# MotorVSense.net
KiCad netlist of a schematic drawn in Altium Designer
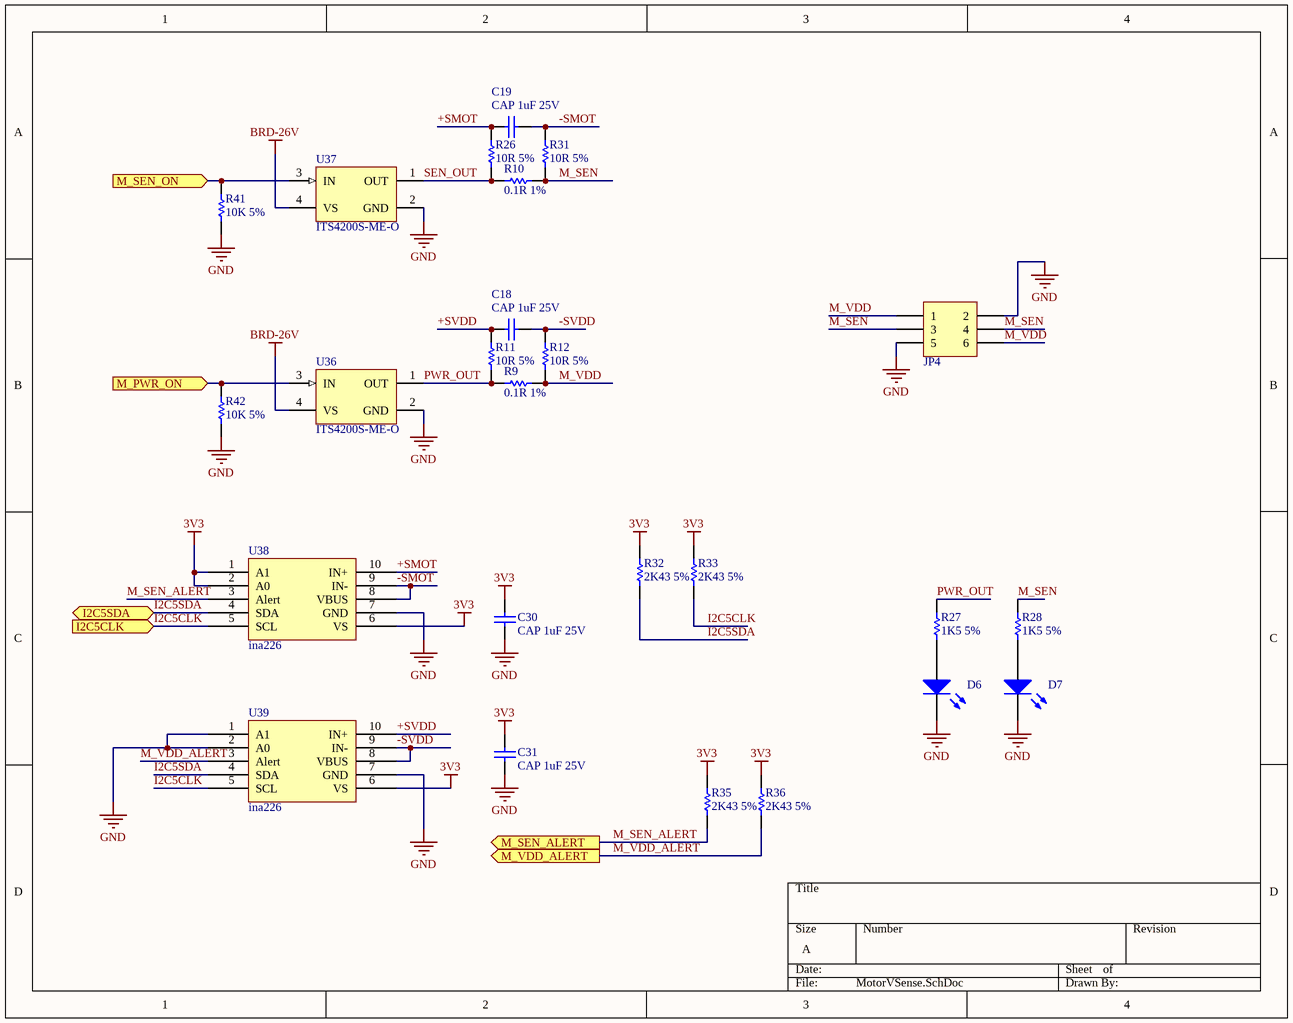
[diagram p0: MotorVSense.SchDoc]

(export (version "E")
  (design (tool "Eeschema 10.0.6"))
  (components
    (comp (ref "C18")
      (value "CAP 1uF 25V")
      (footprint "CAPC0603(1608)100_M")
      (description "CAP 1uF 25V Â±0.25pF 0603 (1608 Metric) Thickness 1mm SMD")
      (fields (field (name "TOLERANCE") "Â±0.25pF"))
      (libsource (lib "Altium Content Vault") (part "CMP-1035-00037-1"))
    )
    (comp (ref "C19")
      (value "CAP 1uF 25V")
      (footprint "CAPC0603(1608)100_M")
      (description "CAP 1uF 25V Â±0.25pF 0603 (1608 Metric) Thickness 1mm SMD")
      (fields (field (name "TOLERANCE") "Â±0.25pF"))
      (libsource (lib "Altium Content Vault") (part "CMP-1035-00037-1"))
    )
    (comp (ref "C30")
      (value "CAP 1uF 25V")
      (footprint "CAPC0603(1608)100_M")
      (description "CAP 1uF 25V Â±0.25pF 0603 (1608 Metric) Thickness 1mm SMD")
      (fields (field (name "TOLERANCE") "Â±0.25pF"))
      (libsource (lib "Altium Content Vault") (part "CMP-1035-00037-1"))
    )
    (comp (ref "C31")
      (value "CAP 1uF 25V")
      (footprint "CAPC0603(1608)100_M")
      (description "CAP 1uF 25V Â±0.25pF 0603 (1608 Metric) Thickness 1mm SMD")
      (fields (field (name "TOLERANCE") "Â±0.25pF"))
      (libsource (lib "Altium Content Vault") (part "CMP-1035-00037-1"))
    )
    (comp (ref "D6")
      (value "LED")
      (footprint "LED-0603")
      (description "Typical RED, GREEN, YELLOW, AMBER GaAs LED")
      (fields (field (name "PUBLISHER") "Altium Limited"))
      (libsource (lib "HSBNE-Vend") (part "LED"))
    )
    (comp (ref "D7")
      (value "LED")
      (footprint "LED-0603")
      (description "Typical RED, GREEN, YELLOW, AMBER GaAs LED")
      (fields (field (name "PUBLISHER") "Altium Limited"))
      (libsource (lib "HSBNE-Vend") (part "LED"))
    )
    (comp (ref "JP4")
      (value "Header 3x2 2.54mm")
      (footprint "2X3")
      (description "Header, 6-Pin")
      (libsource (lib "HSBNE-Vend") (part "Header 3x2"))
    )
    (comp (ref "R9")
      (value "0.1R 1%")
      (footprint "RESC2010(5025)_M")
      (description "0.1R 2010 1%")
      (fields (field (name "TOLERANCE") "None"))
      (libsource (lib "Altium Content Vault") (part "CMP-1017-00001-1"))
    )
    (comp (ref "R10")
      (value "0.1R 1%")
      (footprint "RESC2010(5025)_M")
      (description "0.1R 2010 1%")
      (fields (field (name "TOLERANCE") "None"))
      (libsource (lib "Altium Content Vault") (part "CMP-1017-00001-1"))
    )
    (comp (ref "R11")
      (value "10R 5%")
      (footprint "RESC0603(1608)_M")
      (description "10R 0.1W 5% 0603 (1608 Metric)  SMD")
      (fields (field (name "TOLERANCE") "5 %") (field (name "POWER") "0.1 W"))
      (libsource (lib "Altium Content Vault") (part "CMP-1012-00026-1"))
    )
    (comp (ref "R12")
      (value "10R 5%")
      (footprint "RESC0603(1608)_M")
      (description "10R 0.1W 5% 0603 (1608 Metric)  SMD")
      (fields (field (name "TOLERANCE") "5 %") (field (name "POWER") "0.1 W"))
      (libsource (lib "Altium Content Vault") (part "CMP-1012-00026-1"))
    )
    (comp (ref "R26")
      (value "10R 5%")
      (footprint "RESC0603(1608)_M")
      (description "10R 0.1W 5% 0603 (1608 Metric)  SMD")
      (fields (field (name "TOLERANCE") "5 %") (field (name "POWER") "0.1 W"))
      (libsource (lib "Altium Content Vault") (part "CMP-1012-00026-1"))
    )
    (comp (ref "R27")
      (value "1K5 5%")
      (footprint "RESC0603(1608)_M")
      (description "1K5 0.1W 5% 0603 (1608 Metric)  SMD")
      (fields (field (name "POWER") "0.1 W") (field (name "TOLERANCE") "5 %"))
      (libsource (lib "Altium Content Vault") (part "CMP-1012-00078-1"))
    )
    (comp (ref "R28")
      (value "1K5 5%")
      (footprint "RESC0603(1608)_M")
      (description "1K5 0.1W 5% 0603 (1608 Metric)  SMD")
      (fields (field (name "POWER") "0.1 W") (field (name "TOLERANCE") "5 %"))
      (libsource (lib "Altium Content Vault") (part "CMP-1012-00078-1"))
    )
    (comp (ref "R31")
      (value "10R 5%")
      (footprint "RESC0603(1608)_M")
      (description "10R 0.1W 5% 0603 (1608 Metric)  SMD")
      (fields (field (name "TOLERANCE") "5 %") (field (name "POWER") "0.1 W"))
      (libsource (lib "Altium Content Vault") (part "CMP-1012-00026-1"))
    )
    (comp (ref "R32")
      (value "2K43 5%")
      (footprint "RESC0603(1608)_M")
      (description "2K43 0.1W 5% 0603 (1608 Metric)  SMD")
      (fields (field (name "TOLERANCE") "5 %") (field (name "POWER") "0.1 W"))
      (libsource (lib "Altium Content Vault") (part "CMP-1012-00083-1"))
    )
    (comp (ref "R33")
      (value "2K43 5%")
      (footprint "RESC0603(1608)_M")
      (description "2K43 0.1W 5% 0603 (1608 Metric)  SMD")
      (fields (field (name "TOLERANCE") "5 %") (field (name "POWER") "0.1 W"))
      (libsource (lib "Altium Content Vault") (part "CMP-1012-00083-1"))
    )
    (comp (ref "R35")
      (value "2K43 5%")
      (footprint "RESC0603(1608)_M")
      (description "2K43 0.1W 5% 0603 (1608 Metric)  SMD")
      (fields (field (name "TOLERANCE") "5 %") (field (name "POWER") "0.1 W"))
      (libsource (lib "Altium Content Vault") (part "CMP-1012-00083-1"))
    )
    (comp (ref "R36")
      (value "2K43 5%")
      (footprint "RESC0603(1608)_M")
      (description "2K43 0.1W 5% 0603 (1608 Metric)  SMD")
      (fields (field (name "TOLERANCE") "5 %") (field (name "POWER") "0.1 W"))
      (libsource (lib "Altium Content Vault") (part "CMP-1012-00083-1"))
    )
    (comp (ref "R41")
      (value "10K 5%")
      (footprint "RESC0603(1608)_M")
      (description "10K 0.1W 5% 0603 (1608 Metric)  SMD")
      (fields (field (name "TOLERANCE") "5 %") (field (name "POWER") "0.1 W"))
      (libsource (lib "Altium Content Vault") (part "CMP-1012-00098-1"))
    )
    (comp (ref "R42")
      (value "10K 5%")
      (footprint "RESC0603(1608)_M")
      (description "10K 0.1W 5% 0603 (1608 Metric)  SMD")
      (fields (field (name "TOLERANCE") "5 %") (field (name "POWER") "0.1 W"))
      (libsource (lib "Altium Content Vault") (part "CMP-1012-00098-1"))
    )
    (comp (ref "U36")
      (value "ITS4200S-ME-O")
      (footprint "INF-SOT223_M")
      (description "Smart High-Side NMOS-Power Switch, 11 to 45 V Operating, -40 to 125 degC, SOT223, Reel, Green")
      (fields (field (name "MANUFACTURER") "Infineon"))
      (libsource (lib "Altium Content Vault") (part "INF-ITS4200S-ME-X-SOT223-4"))
    )
    (comp (ref "U37")
      (value "ITS4200S-ME-O")
      (footprint "INF-SOT223_M")
      (description "Smart High-Side NMOS-Power Switch, 11 to 45 V Operating, -40 to 125 degC, SOT223, Reel, Green")
      (fields (field (name "MANUFACTURER") "Infineon"))
      (libsource (lib "Altium Content Vault") (part "INF-ITS4200S-ME-X-SOT223-4"))
    )
    (comp (ref "U38") (value "ina226") (footprint "SP10") (libsource (lib "HSBNE-Vend") (part "ina226")))
    (comp (ref "U39") (value "ina226") (footprint "SP10") (libsource (lib "HSBNE-Vend") (part "ina226")))
  )
  (nets
    (net (code "1") (name "/+SMOT") (class "Default")
      (node (ref "C19") (pin "2") (pinfunction "2_2") (pintype "passive"))
      (node (ref "R26") (pin "2") (pinfunction "2_2") (pintype "passive"))
      (node (ref "U38") (pin "10") (pinfunction "IN+_10") (pintype "passive"))
    )
    (net (code "2") (name "/+SVDD") (class "Default")
      (node (ref "C18") (pin "2") (pinfunction "2_2") (pintype "passive"))
      (node (ref "R11") (pin "2") (pinfunction "2_2") (pintype "passive"))
      (node (ref "U39") (pin "10") (pinfunction "IN+_10") (pintype "passive"))
    )
    (net (code "3") (name "/-SMOT") (class "Default")
      (node (ref "C19") (pin "1") (pinfunction "1_1") (pintype "passive"))
      (node (ref "R31") (pin "2") (pinfunction "2_2") (pintype "passive"))
      (node (ref "U38") (pin "8") (pinfunction "VBUS_8") (pintype "passive"))
      (node (ref "U38") (pin "9") (pinfunction "IN-_9") (pintype "passive"))
    )
    (net (code "4") (name "/-SVDD") (class "Default")
      (node (ref "C18") (pin "1") (pinfunction "1_1") (pintype "passive"))
      (node (ref "R12") (pin "2") (pinfunction "2_2") (pintype "passive"))
      (node (ref "U39") (pin "8") (pinfunction "VBUS_8") (pintype "passive"))
      (node (ref "U39") (pin "9") (pinfunction "IN-_9") (pintype "passive"))
    )
    (net (code "5") (name "/I2C5CLK") (class "Default")
      (node (ref "R33") (pin "1") (pinfunction "1_1") (pintype "passive"))
      (node (ref "U38") (pin "5") (pinfunction "SCL_5") (pintype "passive"))
      (node (ref "U39") (pin "5") (pinfunction "SCL_5") (pintype "passive"))
    )
    (net (code "6") (name "/I2C5SDA") (class "Default")
      (node (ref "R32") (pin "1") (pinfunction "1_1") (pintype "passive"))
      (node (ref "U38") (pin "4") (pinfunction "SDA_4") (pintype "passive"))
      (node (ref "U39") (pin "4") (pinfunction "SDA_4") (pintype "passive"))
    )
    (net (code "7") (name "/M_PWR_ON") (class "Default")
      (node (ref "R42") (pin "2") (pinfunction "2_2") (pintype "passive"))
      (node (ref "U36") (pin "3") (pinfunction "IN_3") (pintype "input"))
    )
    (net (code "8") (name "/M_SEN") (class "Default")
      (node (ref "JP4") (pin "3") (pinfunction "3_3") (pintype "passive"))
      (node (ref "JP4") (pin "4") (pinfunction "4_4") (pintype "passive"))
      (node (ref "R10") (pin "2") (pinfunction "2_2") (pintype "passive"))
      (node (ref "R28") (pin "2") (pinfunction "2_2") (pintype "passive"))
      (node (ref "R31") (pin "1") (pinfunction "1_1") (pintype "passive"))
    )
    (net (code "9") (name "/M_SEN_ALERT") (class "Default")
      (node (ref "R35") (pin "1") (pinfunction "1_1") (pintype "passive"))
      (node (ref "U38") (pin "3") (pinfunction "Alert_3") (pintype "passive"))
    )
    (net (code "10") (name "/M_SEN_ON") (class "Default")
      (node (ref "R41") (pin "2") (pinfunction "2_2") (pintype "passive"))
      (node (ref "U37") (pin "3") (pinfunction "IN_3") (pintype "input"))
    )
    (net (code "11") (name "/M_VDD") (class "Default")
      (node (ref "JP4") (pin "1") (pinfunction "1_1") (pintype "passive"))
      (node (ref "JP4") (pin "6") (pinfunction "6_6") (pintype "passive"))
      (node (ref "R12") (pin "1") (pinfunction "1_1") (pintype "passive"))
      (node (ref "R9") (pin "2") (pinfunction "2_2") (pintype "passive"))
    )
    (net (code "12") (name "/M_VDD_ALERT") (class "Default")
      (node (ref "R36") (pin "1") (pinfunction "1_1") (pintype "passive"))
      (node (ref "U39") (pin "3") (pinfunction "Alert_3") (pintype "passive"))
    )
    (net (code "13") (name "/PWR_OUT") (class "Default")
      (node (ref "R11") (pin "1") (pinfunction "1_1") (pintype "passive"))
      (node (ref "R27") (pin "2") (pinfunction "2_2") (pintype "passive"))
      (node (ref "R9") (pin "1") (pinfunction "1_1") (pintype "passive"))
      (node (ref "U36") (pin "1") (pinfunction "OUT_1") (pintype "power_in"))
    )
    (net (code "14") (name "/SEN_OUT") (class "Default")
      (node (ref "R10") (pin "1") (pinfunction "1_1") (pintype "passive"))
      (node (ref "R26") (pin "1") (pinfunction "1_1") (pintype "passive"))
      (node (ref "U37") (pin "1") (pinfunction "OUT_1") (pintype "power_in"))
    )
    (net (code "15") (name "3V3") (class "Default")
      (node (ref "C30") (pin "1") (pinfunction "1_1") (pintype "passive"))
      (node (ref "C31") (pin "1") (pinfunction "1_1") (pintype "passive"))
      (node (ref "R32") (pin "2") (pinfunction "2_2") (pintype "passive"))
      (node (ref "R33") (pin "2") (pinfunction "2_2") (pintype "passive"))
      (node (ref "R35") (pin "2") (pinfunction "2_2") (pintype "passive"))
      (node (ref "R36") (pin "2") (pinfunction "2_2") (pintype "passive"))
      (node (ref "U38") (pin "1") (pinfunction "A1_1") (pintype "passive"))
      (node (ref "U38") (pin "2") (pinfunction "A0_2") (pintype "passive"))
      (node (ref "U38") (pin "6") (pinfunction "VS_6") (pintype "passive"))
      (node (ref "U39") (pin "6") (pinfunction "VS_6") (pintype "passive"))
    )
    (net (code "16") (name "BRD-26V") (class "Default")
      (node (ref "U36") (pin "4") (pinfunction "VS_4") (pintype "power_in"))
      (node (ref "U37") (pin "4") (pinfunction "VS_4") (pintype "power_in"))
    )
    (net (code "17") (name "GND") (class "Default")
      (node (ref "C30") (pin "2") (pinfunction "2_2") (pintype "passive"))
      (node (ref "C31") (pin "2") (pinfunction "2_2") (pintype "passive"))
      (node (ref "D6") (pin "2") (pinfunction "K_2") (pintype "passive"))
      (node (ref "D7") (pin "2") (pinfunction "K_2") (pintype "passive"))
      (node (ref "JP4") (pin "2") (pinfunction "2_2") (pintype "passive"))
      (node (ref "JP4") (pin "5") (pinfunction "5_5") (pintype "passive"))
      (node (ref "R41") (pin "1") (pinfunction "1_1") (pintype "passive"))
      (node (ref "R42") (pin "1") (pinfunction "1_1") (pintype "passive"))
      (node (ref "U36") (pin "2") (pinfunction "GND_2") (pintype "power_in"))
      (node (ref "U37") (pin "2") (pinfunction "GND_2") (pintype "power_in"))
      (node (ref "U38") (pin "7") (pinfunction "GND_7") (pintype "passive"))
      (node (ref "U39") (pin "1") (pinfunction "A1_1") (pintype "passive"))
      (node (ref "U39") (pin "2") (pinfunction "A0_2") (pintype "passive"))
      (node (ref "U39") (pin "7") (pinfunction "GND_7") (pintype "passive"))
    )
    (net (code "18") (name "Net-(D6-A)") (class "Default")
      (node (ref "D6") (pin "1") (pinfunction "A_1") (pintype "passive"))
      (node (ref "R27") (pin "1") (pinfunction "1_1") (pintype "passive"))
    )
    (net (code "19") (name "Net-(D7-A)") (class "Default")
      (node (ref "D7") (pin "1") (pinfunction "A_1") (pintype "passive"))
      (node (ref "R28") (pin "1") (pinfunction "1_1") (pintype "passive"))
    )
  )
)
